# AstableMultivibrator-PNP.net
KiCad netlist of a schematic drawn in EAGLE
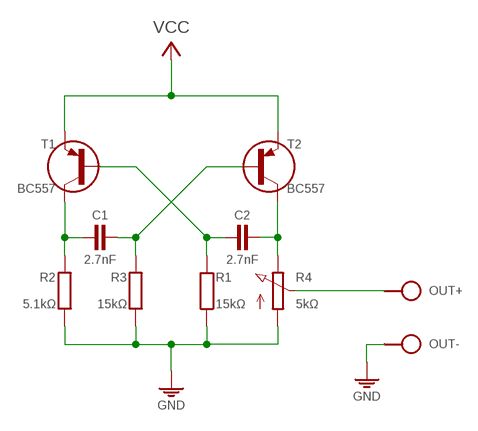
[diagram p0: schematic, sheet 1]

(export (version "E")
  (design (tool "Eeschema 10.0.6"))
  (components
    (comp (ref "C1")
      (value "2.7nF")
      (footprint "eagle-import:C0750-020X044")
      (libsource (lib "eagle-import") (part "C-H075-020X044"))
    )
    (comp (ref "C2")
      (value "2.7nF")
      (footprint "eagle-import:C0750-020X044")
      (libsource (lib "eagle-import") (part "C-H075-020X044"))
    )
    (comp (ref "J1")
      (value "VCC_GNDPWR-L")
      (footprint "eagle-import:PWR-L")
      (libsource (lib "eagle-import") (part "VCC_GNDPWR-L"))
    )
    (comp (ref "OUT")
      (value "SPAD+--+")
      (footprint "eagle-import:SPAD-+")
      (libsource (lib "eagle-import") (part "SPAD+--+"))
    )
    (comp (ref "R1")
      (value "15kΩ")
      (footprint "eagle-import:0202_7-V")
      (libsource (lib "eagle-import") (part "R0202/7-V"))
    )
    (comp (ref "R2")
      (value "5.1kΩ")
      (footprint "eagle-import:0202_7-V")
      (libsource (lib "eagle-import") (part "R0202/7-V"))
    )
    (comp (ref "R3")
      (value "15kΩ")
      (footprint "eagle-import:0202_7-V")
      (libsource (lib "eagle-import") (part "R0202/7-V"))
    )
    (comp (ref "R4")
      (value "5kΩ")
      (footprint "eagle-import:POT-V")
      (libsource (lib "eagle-import") (part "POT-V"))
    )
    (comp (ref "T1")
      (value "BC557")
      (footprint "eagle-import:TO92-CBE")
      (libsource (lib "eagle-import") (part "BC557CBE"))
    )
    (comp (ref "T2")
      (value "BC557")
      (footprint "eagle-import:TO92-CBE")
      (libsource (lib "eagle-import") (part "BC557CBE"))
    )
  )
  (nets
    (net (code "1") (name "GND") (class "Default")
      (node (ref "J1") (pin "1") (pinfunction "GND_1") (pintype "power_in"))
      (node (ref "OUT") (pin "1") (pinfunction "P$1_1") (pintype "passive"))
      (node (ref "R1") (pin "1") (pinfunction "2_1") (pintype "passive"))
      (node (ref "R2") (pin "1") (pinfunction "2_1") (pintype "passive"))
      (node (ref "R3") (pin "1") (pinfunction "2_1") (pintype "passive"))
      (node (ref "R4") (pin "A") (pinfunction "A_A") (pintype "passive"))
    )
    (net (code "2") (name "Net-(C2-Pad2)") (class "Default")
      (node (ref "C2") (pin "2") (pinfunction "2_2") (pintype "passive"))
      (node (ref "R4") (pin "E") (pinfunction "E_E") (pintype "passive"))
      (node (ref "T2") (pin "C") (pinfunction "C_C") (pintype "passive"))
    )
    (net (code "3") (name "Net-(J1A-VCC)") (class "Default")
      (node (ref "J1") (pin "2") (pinfunction "VCC_2") (pintype "power_in"))
      (node (ref "T1") (pin "E") (pinfunction "E_E") (pintype "passive"))
      (node (ref "T2") (pin "E") (pinfunction "E_E") (pintype "passive"))
    )
    (net (code "4") (name "Net-(OUTA-P$1)") (class "Default")
      (node (ref "OUT") (pin "2") (pinfunction "P$1_2") (pintype "passive"))
      (node (ref "R4") (pin "S") (pinfunction "S_S") (pintype "passive"))
    )
    (net (code "5") (name "Net-(R1-1)") (class "Default")
      (node (ref "C2") (pin "1") (pinfunction "1_1") (pintype "passive"))
      (node (ref "R1") (pin "2") (pinfunction "1_2") (pintype "passive"))
      (node (ref "T1") (pin "B") (pinfunction "B_B") (pintype "passive"))
    )
    (net (code "6") (name "Net-(R2-1)") (class "Default")
      (node (ref "C1") (pin "1") (pinfunction "1_1") (pintype "passive"))
      (node (ref "R2") (pin "2") (pinfunction "1_2") (pintype "passive"))
      (node (ref "T1") (pin "C") (pinfunction "C_C") (pintype "passive"))
    )
    (net (code "7") (name "Net-(R3-1)") (class "Default")
      (node (ref "C1") (pin "2") (pinfunction "2_2") (pintype "passive"))
      (node (ref "R3") (pin "2") (pinfunction "1_2") (pintype "passive"))
      (node (ref "T2") (pin "B") (pinfunction "B_B") (pintype "passive"))
    )
  )
)
